# LightSensorsButtons.net
KiCad netlist of a schematic drawn in Altium Designer
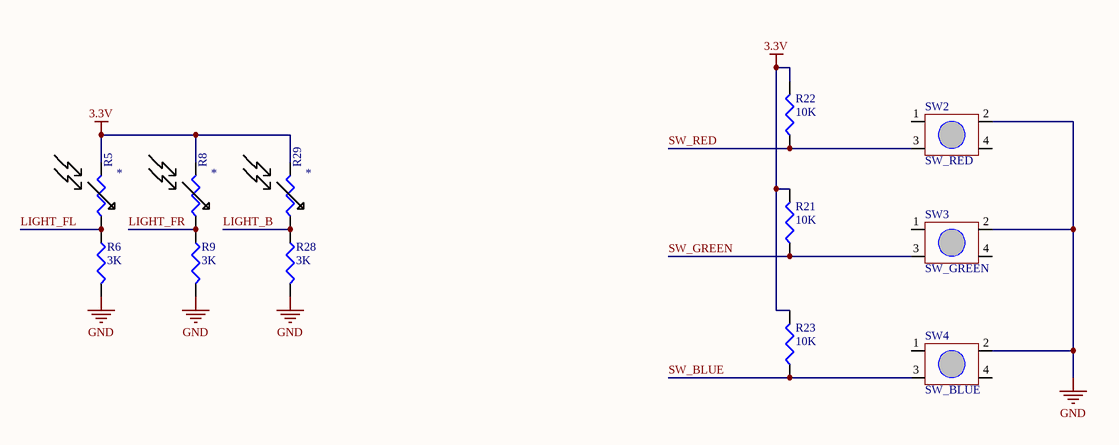
[diagram p0: LightSensorsButtons.SchDoc]

(export (version "E")
  (design (tool "Eeschema 10.0.6"))
  (components
    (comp (ref "R5")
      (value "photoresistor")
      (footprint "photoresistor")
      (fields (field (name "ALTIUM_VALUE") "*"))
      (libsource (lib "mrone") (part "photoresistor"))
    )
    (comp (ref "R6")
      (value "3K")
      (footprint "RESC1608L")
      (description "Resistor")
      (fields (field (name "Comment") "Res3") (field (name "PUBLISHER") "Altium Limited"))
      (libsource (lib "Miscellaneous Devices") (part "Res3"))
    )
    (comp (ref "R8")
      (value "photoresistor")
      (footprint "photoresistor")
      (fields (field (name "ALTIUM_VALUE") "*"))
      (libsource (lib "mrone") (part "photoresistor"))
    )
    (comp (ref "R9")
      (value "3K")
      (footprint "RESC1608L")
      (description "Resistor")
      (fields (field (name "Comment") "Res3") (field (name "PUBLISHER") "Altium Limited"))
      (libsource (lib "Miscellaneous Devices") (part "Res3"))
    )
    (comp (ref "R21")
      (value "10K")
      (footprint "RESC1608L")
      (description "Resistor")
      (fields (field (name "Comment") "Res3") (field (name "PUBLISHER") "Altium Limited"))
      (libsource (lib "Miscellaneous Devices") (part "Res3"))
    )
    (comp (ref "R22")
      (value "10K")
      (footprint "RESC1608L")
      (description "Resistor")
      (fields (field (name "Comment") "Res3") (field (name "PUBLISHER") "Altium Limited"))
      (libsource (lib "Miscellaneous Devices") (part "Res3"))
    )
    (comp (ref "R23")
      (value "10K")
      (footprint "RESC1608L")
      (description "Resistor")
      (fields (field (name "Comment") "Res3") (field (name "PUBLISHER") "Altium Limited"))
      (libsource (lib "Miscellaneous Devices") (part "Res3"))
    )
    (comp (ref "R28")
      (value "3K")
      (footprint "RESC1608L")
      (description "Resistor")
      (fields (field (name "Comment") "Res3") (field (name "PUBLISHER") "Altium Limited"))
      (libsource (lib "Miscellaneous Devices") (part "Res3"))
    )
    (comp (ref "R29")
      (value "photoresistor")
      (footprint "photoresistor")
      (fields (field (name "ALTIUM_VALUE") "*"))
      (libsource (lib "mrone") (part "photoresistor"))
    )
    (comp (ref "SW2")
      (value "SW_RED")
      (footprint "SwitchTall-TL330")
      (libsource (lib "mrone") (part "Switch-TL330"))
    )
    (comp (ref "SW3")
      (value "SW_GREEN")
      (footprint "SwitchTall-TL330")
      (libsource (lib "mrone") (part "Switch-TL330"))
    )
    (comp (ref "SW4")
      (value "SW_BLUE")
      (footprint "SwitchTall-TL330")
      (libsource (lib "mrone") (part "Switch-TL330"))
    )
  )
  (nets
    (net (code "1") (name "/LIGHT_B") (class "Default")
      (node (ref "R28") (pin "1") (pinfunction "1_1") (pintype "passive"))
      (node (ref "R29") (pin "1") (pinfunction "1_1") (pintype "passive"))
    )
    (net (code "2") (name "/LIGHT_FL") (class "Default")
      (node (ref "R5") (pin "1") (pinfunction "1_1") (pintype "passive"))
      (node (ref "R6") (pin "1") (pinfunction "1_1") (pintype "passive"))
    )
    (net (code "3") (name "/LIGHT_FR") (class "Default")
      (node (ref "R8") (pin "1") (pinfunction "1_1") (pintype "passive"))
      (node (ref "R9") (pin "1") (pinfunction "1_1") (pintype "passive"))
    )
    (net (code "4") (name "/SW_BLUE") (class "Default")
      (node (ref "R23") (pin "1") (pinfunction "1_1") (pintype "passive"))
      (node (ref "SW4") (pin "3") (pinfunction "3_3") (pintype "passive"))
    )
    (net (code "5") (name "/SW_GREEN") (class "Default")
      (node (ref "R21") (pin "1") (pinfunction "1_1") (pintype "passive"))
      (node (ref "SW3") (pin "3") (pinfunction "3_3") (pintype "passive"))
    )
    (net (code "6") (name "/SW_RED") (class "Default")
      (node (ref "R22") (pin "1") (pinfunction "1_1") (pintype "passive"))
      (node (ref "SW2") (pin "3") (pinfunction "3_3") (pintype "passive"))
    )
    (net (code "7") (name "3.3V") (class "Default")
      (node (ref "R21") (pin "2") (pinfunction "2_2") (pintype "passive"))
      (node (ref "R22") (pin "2") (pinfunction "2_2") (pintype "passive"))
      (node (ref "R23") (pin "2") (pinfunction "2_2") (pintype "passive"))
      (node (ref "R29") (pin "2") (pinfunction "2_2") (pintype "passive"))
      (node (ref "R5") (pin "2") (pinfunction "2_2") (pintype "passive"))
      (node (ref "R8") (pin "2") (pinfunction "2_2") (pintype "passive"))
    )
    (net (code "8") (name "GND") (class "Default")
      (node (ref "R28") (pin "2") (pinfunction "2_2") (pintype "passive"))
      (node (ref "R6") (pin "2") (pinfunction "2_2") (pintype "passive"))
      (node (ref "R9") (pin "2") (pinfunction "2_2") (pintype "passive"))
      (node (ref "SW2") (pin "2") (pinfunction "2_2") (pintype "passive"))
      (node (ref "SW3") (pin "2") (pinfunction "2_2") (pintype "passive"))
      (node (ref "SW4") (pin "2") (pinfunction "2_2") (pintype "passive"))
    )
    (net (code "9") (name "unconnected-(SW2-Pad1)") (class "Default")
      (node (ref "SW2") (pin "1") (pinfunction "1_1") (pintype "passive"))
    )
    (net (code "10") (name "unconnected-(SW2-Pad4)") (class "Default")
      (node (ref "SW2") (pin "4") (pinfunction "4_4") (pintype "passive"))
    )
    (net (code "11") (name "unconnected-(SW3-Pad1)") (class "Default")
      (node (ref "SW3") (pin "1") (pinfunction "1_1") (pintype "passive"))
    )
    (net (code "12") (name "unconnected-(SW3-Pad4)") (class "Default")
      (node (ref "SW3") (pin "4") (pinfunction "4_4") (pintype "passive"))
    )
    (net (code "13") (name "unconnected-(SW4-Pad1)") (class "Default")
      (node (ref "SW4") (pin "1") (pinfunction "1_1") (pintype "passive"))
    )
    (net (code "14") (name "unconnected-(SW4-Pad4)") (class "Default")
      (node (ref "SW4") (pin "4") (pinfunction "4_4") (pintype "passive"))
    )
  )
)
